# MTK3339.net
KiCad netlist of a schematic drawn in EAGLE
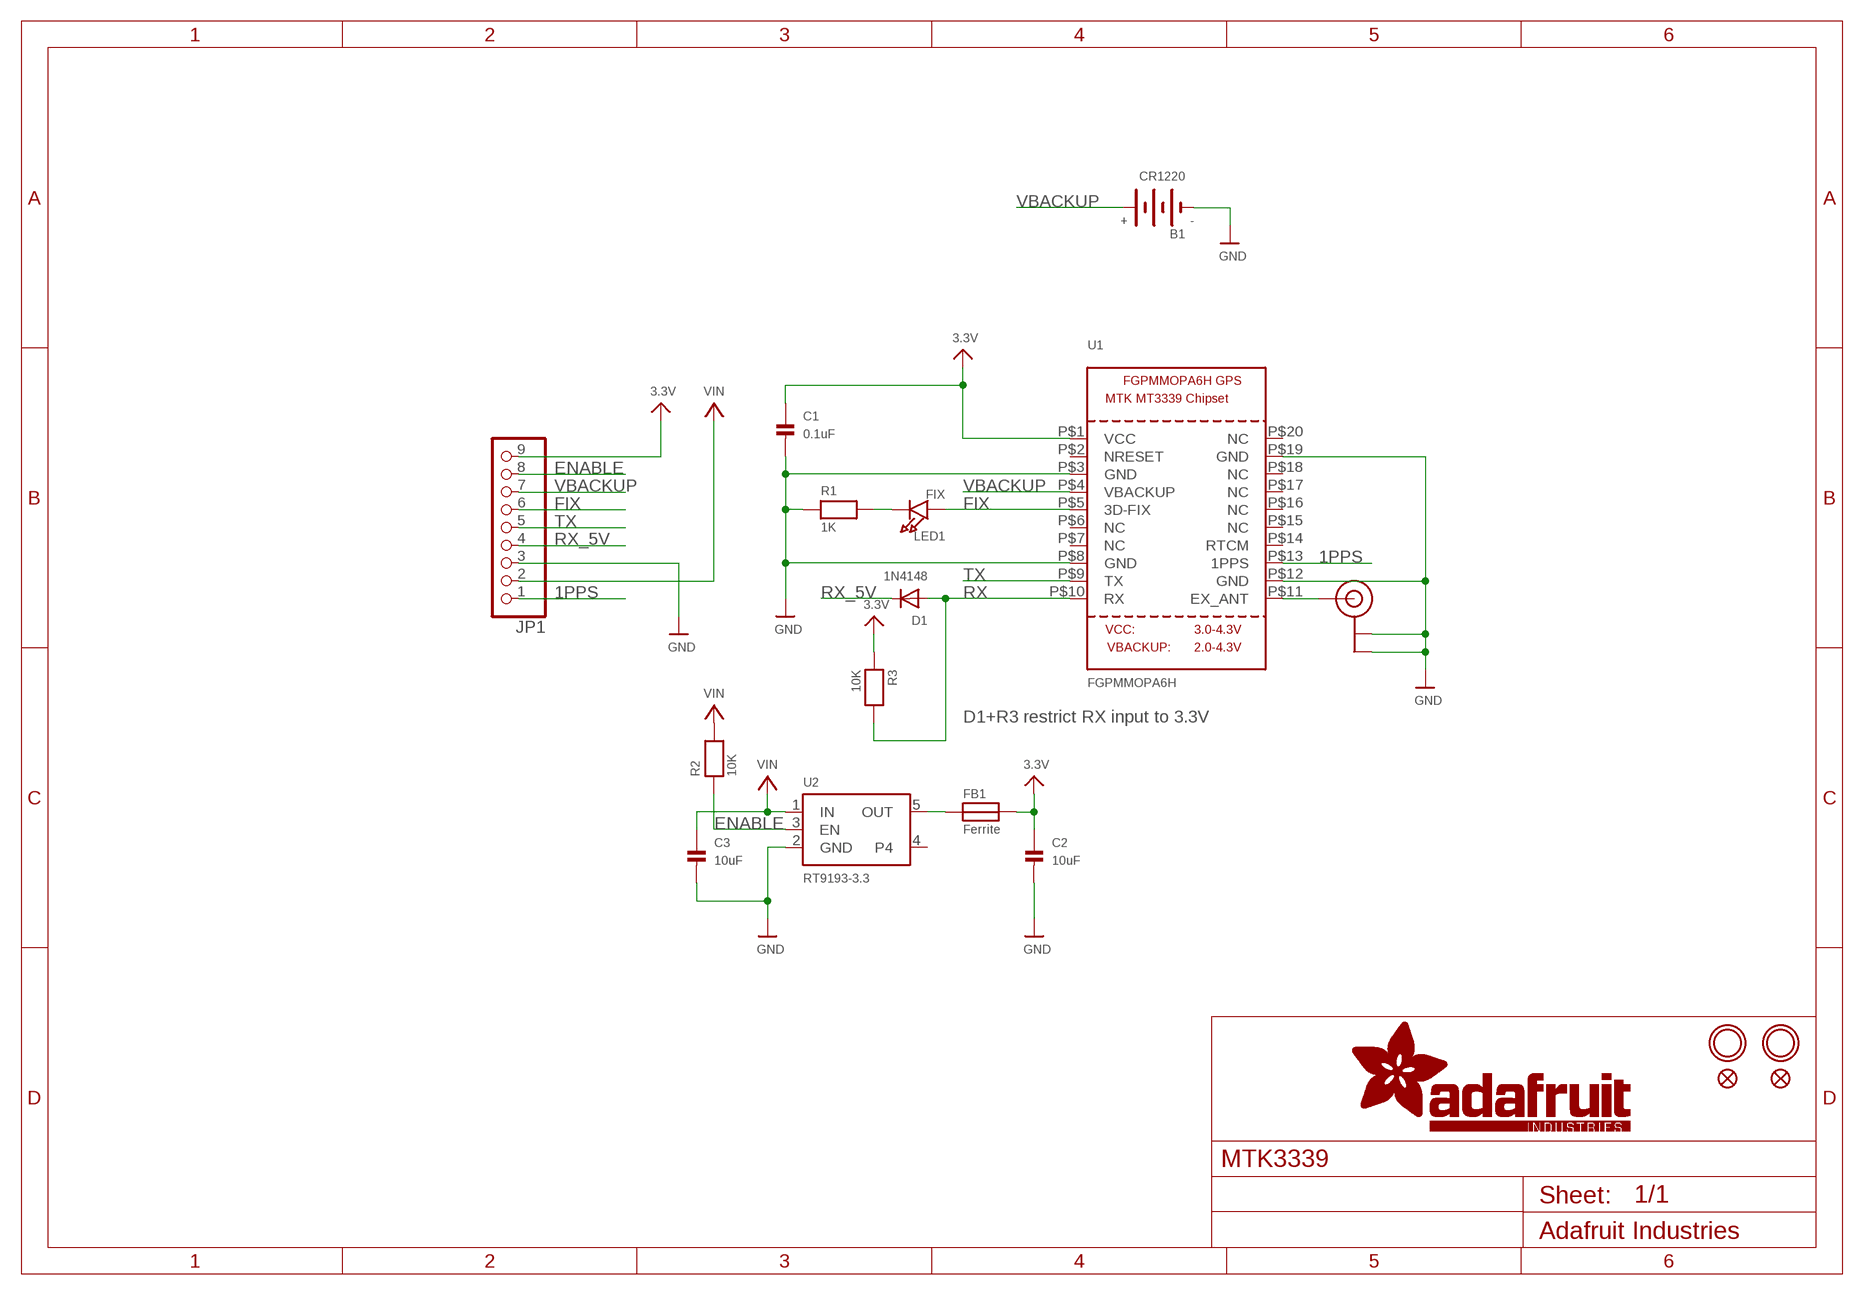
[diagram p0: schematic, sheet 1]

(export (version "E")
  (design (tool "Eeschema 10.0.6"))
  (components
    (comp (ref "B1")
      (value "CR1220")
      (footprint "eagle-import:CR1220")
      (libsource (lib "eagle-import") (part "BATTERYCR1220_SMT"))
    )
    (comp (ref "C1")
      (value "0.1uF")
      (footprint "eagle-import:0805")
      (libsource (lib "eagle-import") (part "CAP_CERAMIC0805"))
    )
    (comp (ref "C2")
      (value "10uF")
      (footprint "eagle-import:0805")
      (libsource (lib "eagle-import") (part "CAP_CERAMIC0805"))
    )
    (comp (ref "C3")
      (value "10uF")
      (footprint "eagle-import:0805")
      (libsource (lib "eagle-import") (part "CAP_CERAMIC0805"))
    )
    (comp (ref "D1")
      (value "1N4148")
      (footprint "eagle-import:SOD-323F")
      (libsource (lib "eagle-import") (part "DIODESOD-323F"))
    )
    (comp (ref "FB1")
      (value "Ferrite")
      (footprint "eagle-import:0805")
      (libsource (lib "eagle-import") (part "FERRITE0805"))
    )
    (comp (ref "FID1")
      (value "FIDUCIAL\"\"")
      (footprint "eagle-import:FIDUCIAL_1MM")
      (libsource (lib "eagle-import") (part "FIDUCIAL{dblquote}{dblquote}"))
    )
    (comp (ref "FID2")
      (value "FIDUCIAL\"\"")
      (footprint "eagle-import:FIDUCIAL_1MM")
      (libsource (lib "eagle-import") (part "FIDUCIAL{dblquote}{dblquote}"))
    )
    (comp (ref "JP1")
      (value "HEADER-1X970MIL")
      (footprint "eagle-import:1X09_ROUND_70")
      (libsource (lib "eagle-import") (part "HEADER-1X970MIL"))
    )
    (comp (ref "LED1")
      (value "FIX")
      (footprint "eagle-import:CHIPLED_0805")
      (libsource (lib "eagle-import") (part "LED0805"))
    )
    (comp (ref "R1")
      (value "1K")
      (footprint "eagle-import:0805")
      (libsource (lib "eagle-import") (part "RESISTOR0805"))
    )
    (comp (ref "R2")
      (value "10K")
      (footprint "eagle-import:0805")
      (libsource (lib "eagle-import") (part "RESISTOR0805"))
    )
    (comp (ref "R3")
      (value "10K")
      (footprint "eagle-import:0805")
      (libsource (lib "eagle-import") (part "RESISTOR0805"))
    )
    (comp (ref "U$8")
      (value "MOUNTINGHOLE2.0")
      (footprint "eagle-import:MOUNTINGHOLE_2.0_PLATED")
      (libsource (lib "eagle-import") (part "MOUNTINGHOLE2.0"))
    )
    (comp (ref "U$9")
      (value "MOUNTINGHOLE2.0")
      (footprint "eagle-import:MOUNTINGHOLE_2.0_PLATED")
      (libsource (lib "eagle-import") (part "MOUNTINGHOLE2.0"))
    )
    (comp (ref "U$20")
      (value "U.FL")
      (footprint "eagle-import:U.FL")
      (libsource (lib "eagle-import") (part "U.FL"))
    )
    (comp (ref "U1")
      (value "FGPMMOPA6H")
      (footprint "eagle-import:FGPMMOPA6H")
      (libsource (lib "eagle-import") (part "GPS_FGPMMOPA6H"))
    )
    (comp (ref "U2")
      (value "RT9193-3.3")
      (footprint "eagle-import:SOT23-5")
      (libsource (lib "eagle-import") (part "VREG_SOT23-5"))
    )
  )
  (nets
    (net (code "1") (name "/1PPS") (class "Default")
      (node (ref "JP1") (pin "1") (pinfunction "1_1") (pintype "passive"))
      (node (ref "U1") (pin "P$13") (pinfunction "1PPS_P$13") (pintype "bidirectional"))
    )
    (net (code "2") (name "/ENABLE") (class "Default")
      (node (ref "JP1") (pin "8") (pinfunction "8_8") (pintype "passive"))
      (node (ref "R2") (pin "1") (pinfunction "1_1") (pintype "passive"))
      (node (ref "U2") (pin "3") (pinfunction "EN_3") (pintype "bidirectional"))
    )
    (net (code "3") (name "/FIX") (class "Default")
      (node (ref "JP1") (pin "6") (pinfunction "6_6") (pintype "passive"))
      (node (ref "LED1") (pin "A") (pinfunction "A_A") (pintype "passive"))
      (node (ref "U1") (pin "P$5") (pinfunction "3D-FIX_P$5") (pintype "bidirectional"))
    )
    (net (code "4") (name "/RX") (class "Default")
      (node (ref "D1") (pin "A") (pinfunction "A_A") (pintype "passive"))
      (node (ref "R3") (pin "2") (pinfunction "2_2") (pintype "passive"))
      (node (ref "U1") (pin "P$10") (pinfunction "RX_P$10") (pintype "bidirectional"))
    )
    (net (code "5") (name "/RX_5V") (class "Default")
      (node (ref "D1") (pin "C") (pinfunction "C_C") (pintype "passive"))
      (node (ref "JP1") (pin "4") (pinfunction "4_4") (pintype "passive"))
    )
    (net (code "6") (name "/TX") (class "Default")
      (node (ref "JP1") (pin "5") (pinfunction "5_5") (pintype "passive"))
      (node (ref "U1") (pin "P$9") (pinfunction "TX_P$9") (pintype "bidirectional"))
    )
    (net (code "7") (name "/VBACKUP") (class "Default")
      (node (ref "B1") (pin "+$1") (pinfunction "+_+$1") (pintype "passive"))
      (node (ref "JP1") (pin "7") (pinfunction "7_7") (pintype "passive"))
      (node (ref "U1") (pin "P$4") (pinfunction "VBACKUP_P$4") (pintype "bidirectional"))
    )
    (net (code "8") (name "3.3V") (class "Default")
      (node (ref "C1") (pin "1") (pinfunction "P$1_1") (pintype "passive"))
      (node (ref "C2") (pin "1") (pinfunction "P$1_1") (pintype "passive"))
      (node (ref "FB1") (pin "2") (pinfunction "P$2_2") (pintype "bidirectional"))
      (node (ref "JP1") (pin "9") (pinfunction "9_9") (pintype "passive"))
      (node (ref "R3") (pin "1") (pinfunction "1_1") (pintype "passive"))
      (node (ref "U1") (pin "P$1") (pinfunction "VCC_P$1") (pintype "bidirectional"))
    )
    (net (code "9") (name "GND") (class "Default")
      (node (ref "B1") (pin "-") (pinfunction "-_-") (pintype "passive"))
      (node (ref "C1") (pin "2") (pinfunction "P$2_2") (pintype "passive"))
      (node (ref "C2") (pin "2") (pinfunction "P$2_2") (pintype "passive"))
      (node (ref "C3") (pin "2") (pinfunction "P$2_2") (pintype "passive"))
      (node (ref "JP1") (pin "3") (pinfunction "3_3") (pintype "passive"))
      (node (ref "R1") (pin "1") (pinfunction "1_1") (pintype "passive"))
      (node (ref "U$20") (pin "P$1") (pinfunction "GND_P$1") (pintype "bidirectional"))
      (node (ref "U$20") (pin "P$2") (pinfunction "GND_P$2") (pintype "bidirectional"))
      (node (ref "U1") (pin "P$12") (pinfunction "GND_P$12") (pintype "bidirectional"))
      (node (ref "U1") (pin "P$19") (pinfunction "GND_P$19") (pintype "bidirectional"))
      (node (ref "U1") (pin "P$3") (pinfunction "GND_P$3") (pintype "bidirectional"))
      (node (ref "U1") (pin "P$8") (pinfunction "GND_P$8") (pintype "bidirectional"))
      (node (ref "U2") (pin "2") (pinfunction "GND_2") (pintype "bidirectional"))
    )
    (net (code "10") (name "Net-(FB1-P$1)") (class "Default")
      (node (ref "FB1") (pin "1") (pinfunction "P$1_1") (pintype "bidirectional"))
      (node (ref "U2") (pin "5") (pinfunction "OUT_5") (pintype "bidirectional"))
    )
    (net (code "11") (name "Net-(LED1-PadC)") (class "Default")
      (node (ref "LED1") (pin "C") (pinfunction "C_C") (pintype "passive"))
      (node (ref "R1") (pin "2") (pinfunction "2_2") (pintype "passive"))
    )
    (net (code "12") (name "Net-(U$20-SIGNAL)") (class "Default")
      (node (ref "U$20") (pin "P$3") (pinfunction "SIGNAL_P$3") (pintype "bidirectional"))
      (node (ref "U1") (pin "P$11") (pinfunction "EX_ANT_P$11") (pintype "bidirectional"))
    )
    (net (code "13") (name "VIN") (class "Default")
      (node (ref "C3") (pin "1") (pinfunction "P$1_1") (pintype "passive"))
      (node (ref "JP1") (pin "2") (pinfunction "2_2") (pintype "passive"))
      (node (ref "R2") (pin "2") (pinfunction "2_2") (pintype "passive"))
      (node (ref "U2") (pin "1") (pinfunction "IN_1") (pintype "bidirectional"))
    )
    (net (code "14") (name "unconnected-(U1-NC-PadP$6)") (class "Default")
      (node (ref "U1") (pin "P$6") (pinfunction "NC_P$6") (pintype "bidirectional"))
    )
    (net (code "15") (name "unconnected-(U1-NC-PadP$7)") (class "Default")
      (node (ref "U1") (pin "P$7") (pinfunction "NC_P$7") (pintype "bidirectional"))
    )
    (net (code "16") (name "unconnected-(U1-NC-PadP$15)") (class "Default")
      (node (ref "U1") (pin "P$15") (pinfunction "NC_P$15") (pintype "bidirectional"))
    )
    (net (code "17") (name "unconnected-(U1-NC-PadP$16)") (class "Default")
      (node (ref "U1") (pin "P$16") (pinfunction "NC_P$16") (pintype "bidirectional"))
    )
    (net (code "18") (name "unconnected-(U1-NC-PadP$17)") (class "Default")
      (node (ref "U1") (pin "P$17") (pinfunction "NC_P$17") (pintype "bidirectional"))
    )
    (net (code "19") (name "unconnected-(U1-NC-PadP$18)") (class "Default")
      (node (ref "U1") (pin "P$18") (pinfunction "NC_P$18") (pintype "bidirectional"))
    )
    (net (code "20") (name "unconnected-(U1-NC-PadP$20)") (class "Default")
      (node (ref "U1") (pin "P$20") (pinfunction "NC_P$20") (pintype "bidirectional"))
    )
    (net (code "21") (name "unconnected-(U1-NRESET-PadP$2)") (class "Default")
      (node (ref "U1") (pin "P$2") (pinfunction "NRESET_P$2") (pintype "bidirectional"))
    )
    (net (code "22") (name "unconnected-(U1-RTCM-PadP$14)") (class "Default")
      (node (ref "U1") (pin "P$14") (pinfunction "RTCM_P$14") (pintype "bidirectional"))
    )
    (net (code "23") (name "unconnected-(U2-P4-Pad4)") (class "Default")
      (node (ref "U2") (pin "4") (pinfunction "P4_4") (pintype "bidirectional"))
    )
  )
)
